# LyteLab_Base_Rev4.net
KiCad netlist of a schematic drawn in EAGLE
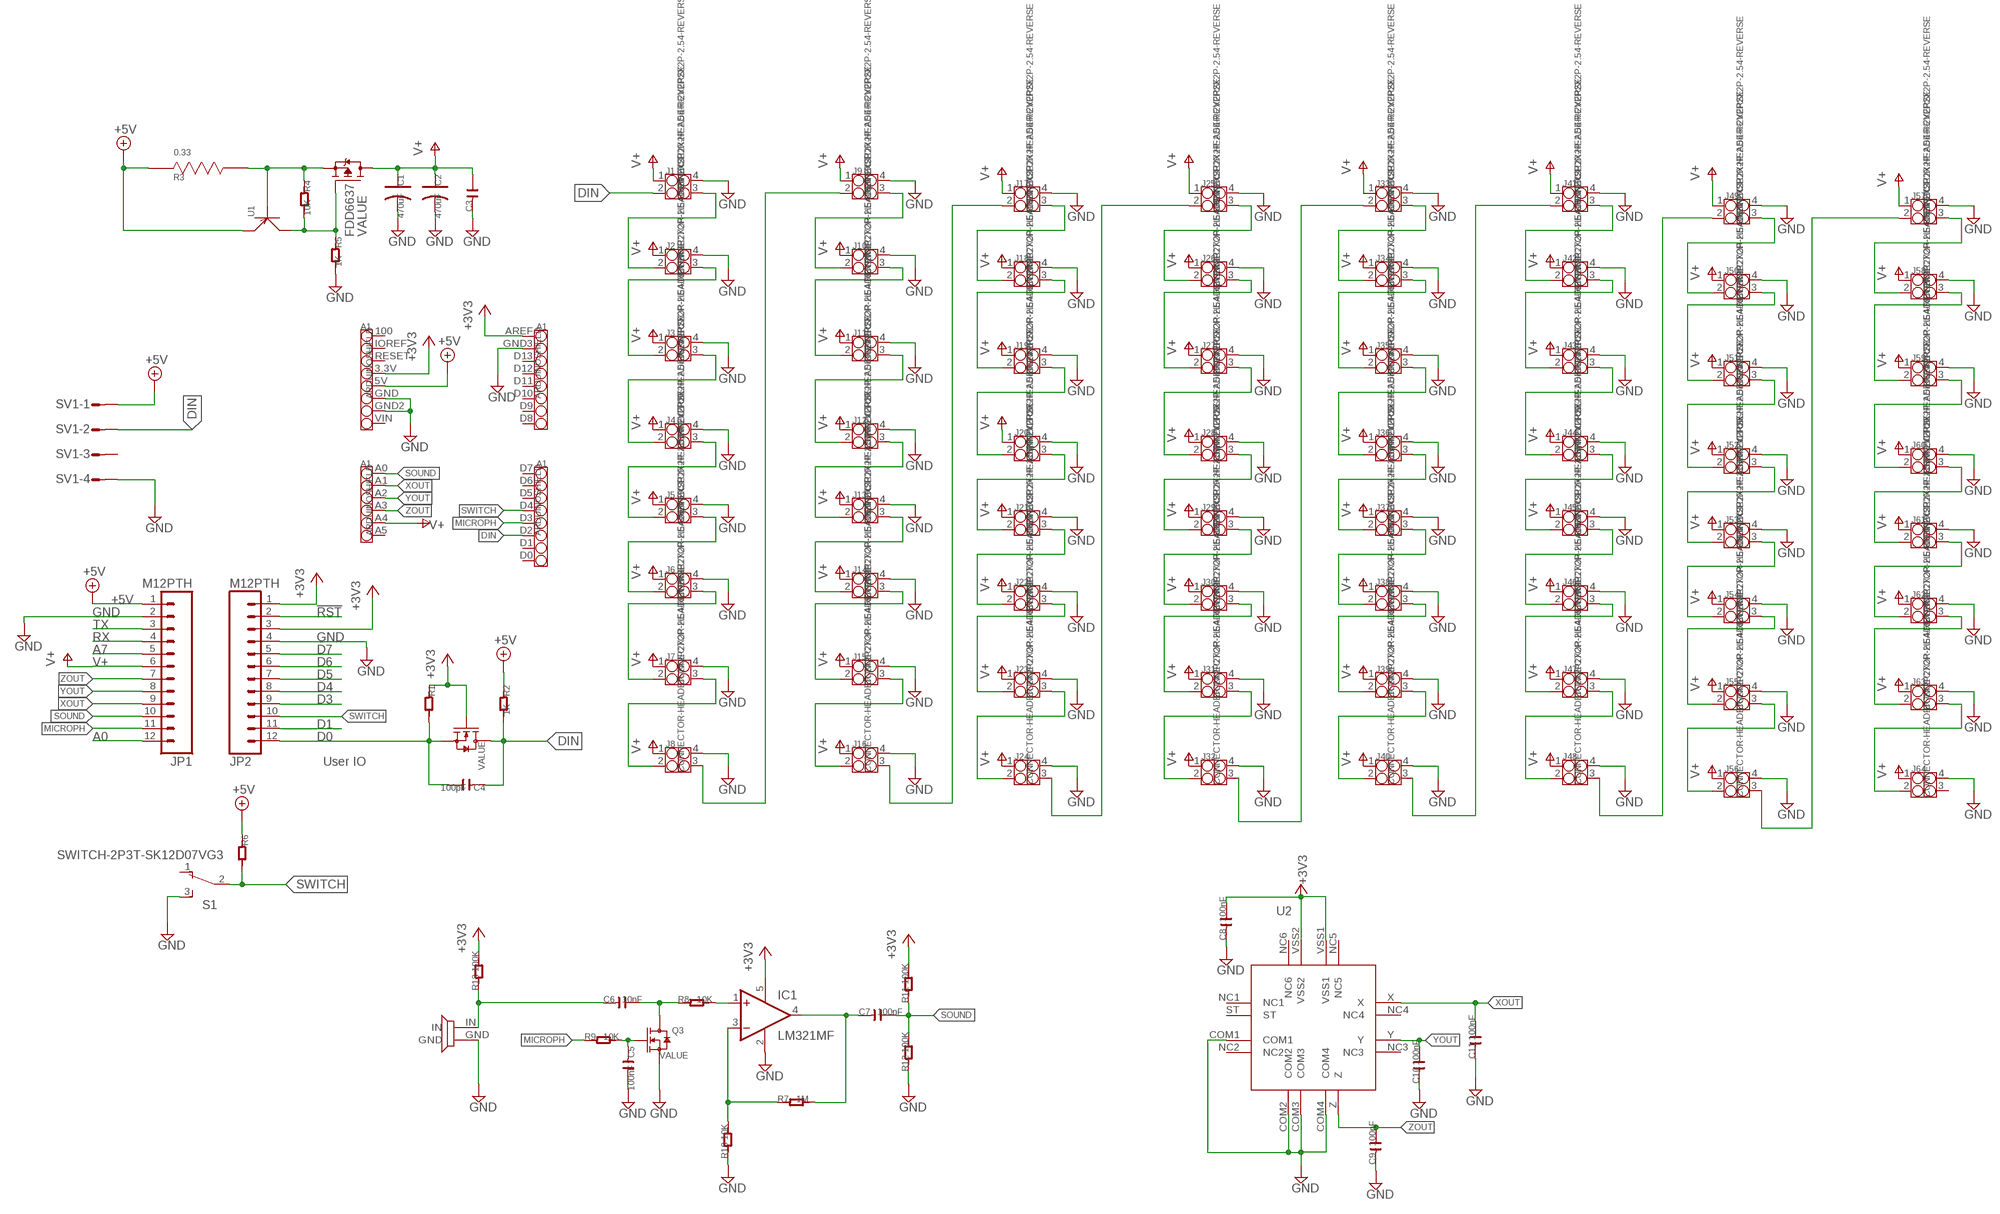
[diagram p0: schematic, sheet 1]

(export (version "E")
  (design (tool "Eeschema 10.0.6"))
  (components
    (comp (ref "2N7002")
      (value "MOSFET-N-044020001")
      (footprint "eagle-import:SOT23")
      (libsource (lib "eagle-import") (part "MOSFET-N-044020001"))
    )
    (comp (ref "A1")
      (value "ARDUINOSHIELD")
      (footprint "eagle-import:ARDUINOSHIELD")
      (libsource (lib "eagle-import") (part "ARDUINOSHIELD"))
    )
    (comp (ref "C1")
      (value "470uF")
      (footprint "eagle-import:CAPACITOR-E5-8.5")
      (libsource (lib "eagle-import") (part "C-POLARCAPACITOR-E5-8.5"))
    )
    (comp (ref "C2")
      (value "470uF")
      (footprint "eagle-import:CAPACITOR-E5-8.5")
      (libsource (lib "eagle-import") (part "C-POLARCAPACITOR-E5-8.5"))
    )
    (comp (ref "C3")
      (value "C-0603")
      (footprint "eagle-import:C0603")
      (libsource (lib "eagle-import") (part "C-0603"))
    )
    (comp (ref "C4")
      (value "100pF")
      (footprint "eagle-import:C0603")
      (libsource (lib "eagle-import") (part "C-0603"))
    )
    (comp (ref "C5")
      (value "100nF")
      (footprint "eagle-import:C0603")
      (libsource (lib "eagle-import") (part "C-0603"))
    )
    (comp (ref "C6")
      (value "10nF")
      (footprint "eagle-import:C0603")
      (libsource (lib "eagle-import") (part "C-0603"))
    )
    (comp (ref "C7")
      (value "100nF")
      (footprint "eagle-import:C0603")
      (libsource (lib "eagle-import") (part "C-0603"))
    )
    (comp (ref "C8")
      (value "100nF")
      (footprint "eagle-import:C0603")
      (libsource (lib "eagle-import") (part "C-0603"))
    )
    (comp (ref "C9")
      (value "100nF")
      (footprint "eagle-import:C0603")
      (libsource (lib "eagle-import") (part "C-0603"))
    )
    (comp (ref "C10")
      (value "100nF")
      (footprint "eagle-import:C0603")
      (libsource (lib "eagle-import") (part "C-0603"))
    )
    (comp (ref "C11")
      (value "100nF")
      (footprint "eagle-import:C0603")
      (libsource (lib "eagle-import") (part "C-0603"))
    )
    (comp (ref "FDD6637")
      (value "FDD4141TO252")
      (footprint "eagle-import:TO252")
      (libsource (lib "eagle-import") (part "FDD4141TO252"))
    )
    (comp (ref "IC1")
      (value "LM321MF")
      (footprint "eagle-import:SOT23-5")
      (libsource (lib "eagle-import") (part "LM321?MF"))
    )
    (comp (ref "J1")
      (value "CONNECTOR-HEADER-2X2P2X2P-2.54-REVERSE")
      (footprint "eagle-import:2X2P-2.54-REVERSE")
      (libsource (lib "eagle-import") (part "CONNECTOR-HEADER-2X2P2X2P-2.54-REVERSE"))
    )
    (comp (ref "J2")
      (value "CONNECTOR-HEADER-2X2P2X2P-2.54-REVERSE")
      (footprint "eagle-import:2X2P-2.54-REVERSE")
      (libsource (lib "eagle-import") (part "CONNECTOR-HEADER-2X2P2X2P-2.54-REVERSE"))
    )
    (comp (ref "J3")
      (value "CONNECTOR-HEADER-2X2P2X2P-2.54-REVERSE")
      (footprint "eagle-import:2X2P-2.54-REVERSE")
      (libsource (lib "eagle-import") (part "CONNECTOR-HEADER-2X2P2X2P-2.54-REVERSE"))
    )
    (comp (ref "J4")
      (value "CONNECTOR-HEADER-2X2P2X2P-2.54-REVERSE")
      (footprint "eagle-import:2X2P-2.54-REVERSE")
      (libsource (lib "eagle-import") (part "CONNECTOR-HEADER-2X2P2X2P-2.54-REVERSE"))
    )
    (comp (ref "J5")
      (value "CONNECTOR-HEADER-2X2P2X2P-2.54-REVERSE")
      (footprint "eagle-import:2X2P-2.54-REVERSE")
      (libsource (lib "eagle-import") (part "CONNECTOR-HEADER-2X2P2X2P-2.54-REVERSE"))
    )
    (comp (ref "J6")
      (value "CONNECTOR-HEADER-2X2P2X2P-2.54-REVERSE")
      (footprint "eagle-import:2X2P-2.54-REVERSE")
      (libsource (lib "eagle-import") (part "CONNECTOR-HEADER-2X2P2X2P-2.54-REVERSE"))
    )
    (comp (ref "J7")
      (value "CONNECTOR-HEADER-2X2P2X2P-2.54-REVERSE")
      (footprint "eagle-import:2X2P-2.54-REVERSE")
      (libsource (lib "eagle-import") (part "CONNECTOR-HEADER-2X2P2X2P-2.54-REVERSE"))
    )
    (comp (ref "J8")
      (value "CONNECTOR-HEADER-2X2P2X2P-2.54-REVERSE")
      (footprint "eagle-import:2X2P-2.54-REVERSE")
      (libsource (lib "eagle-import") (part "CONNECTOR-HEADER-2X2P2X2P-2.54-REVERSE"))
    )
    (comp (ref "J9")
      (value "CONNECTOR-HEADER-2X2P2X2P-2.54-REVERSE")
      (footprint "eagle-import:2X2P-2.54-REVERSE")
      (libsource (lib "eagle-import") (part "CONNECTOR-HEADER-2X2P2X2P-2.54-REVERSE"))
    )
    (comp (ref "J10")
      (value "CONNECTOR-HEADER-2X2P2X2P-2.54-REVERSE")
      (footprint "eagle-import:2X2P-2.54-REVERSE")
      (libsource (lib "eagle-import") (part "CONNECTOR-HEADER-2X2P2X2P-2.54-REVERSE"))
    )
    (comp (ref "J11")
      (value "CONNECTOR-HEADER-2X2P2X2P-2.54-REVERSE")
      (footprint "eagle-import:2X2P-2.54-REVERSE")
      (libsource (lib "eagle-import") (part "CONNECTOR-HEADER-2X2P2X2P-2.54-REVERSE"))
    )
    (comp (ref "J12")
      (value "CONNECTOR-HEADER-2X2P2X2P-2.54-REVERSE")
      (footprint "eagle-import:2X2P-2.54-REVERSE")
      (libsource (lib "eagle-import") (part "CONNECTOR-HEADER-2X2P2X2P-2.54-REVERSE"))
    )
    (comp (ref "J13")
      (value "CONNECTOR-HEADER-2X2P2X2P-2.54-REVERSE")
      (footprint "eagle-import:2X2P-2.54-REVERSE")
      (libsource (lib "eagle-import") (part "CONNECTOR-HEADER-2X2P2X2P-2.54-REVERSE"))
    )
    (comp (ref "J14")
      (value "CONNECTOR-HEADER-2X2P2X2P-2.54-REVERSE")
      (footprint "eagle-import:2X2P-2.54-REVERSE")
      (libsource (lib "eagle-import") (part "CONNECTOR-HEADER-2X2P2X2P-2.54-REVERSE"))
    )
    (comp (ref "J15")
      (value "CONNECTOR-HEADER-2X2P2X2P-2.54-REVERSE")
      (footprint "eagle-import:2X2P-2.54-REVERSE")
      (libsource (lib "eagle-import") (part "CONNECTOR-HEADER-2X2P2X2P-2.54-REVERSE"))
    )
    (comp (ref "J16")
      (value "CONNECTOR-HEADER-2X2P2X2P-2.54-REVERSE")
      (footprint "eagle-import:2X2P-2.54-REVERSE")
      (libsource (lib "eagle-import") (part "CONNECTOR-HEADER-2X2P2X2P-2.54-REVERSE"))
    )
    (comp (ref "J17")
      (value "CONNECTOR-HEADER-2X2P2X2P-2.54-REVERSE")
      (footprint "eagle-import:2X2P-2.54-REVERSE")
      (libsource (lib "eagle-import") (part "CONNECTOR-HEADER-2X2P2X2P-2.54-REVERSE"))
    )
    (comp (ref "J18")
      (value "CONNECTOR-HEADER-2X2P2X2P-2.54-REVERSE")
      (footprint "eagle-import:2X2P-2.54-REVERSE")
      (libsource (lib "eagle-import") (part "CONNECTOR-HEADER-2X2P2X2P-2.54-REVERSE"))
    )
    (comp (ref "J19")
      (value "CONNECTOR-HEADER-2X2P2X2P-2.54-REVERSE")
      (footprint "eagle-import:2X2P-2.54-REVERSE")
      (libsource (lib "eagle-import") (part "CONNECTOR-HEADER-2X2P2X2P-2.54-REVERSE"))
    )
    (comp (ref "J20")
      (value "CONNECTOR-HEADER-2X2P2X2P-2.54-REVERSE")
      (footprint "eagle-import:2X2P-2.54-REVERSE")
      (libsource (lib "eagle-import") (part "CONNECTOR-HEADER-2X2P2X2P-2.54-REVERSE"))
    )
    (comp (ref "J21")
      (value "CONNECTOR-HEADER-2X2P2X2P-2.54-REVERSE")
      (footprint "eagle-import:2X2P-2.54-REVERSE")
      (libsource (lib "eagle-import") (part "CONNECTOR-HEADER-2X2P2X2P-2.54-REVERSE"))
    )
    (comp (ref "J22")
      (value "CONNECTOR-HEADER-2X2P2X2P-2.54-REVERSE")
      (footprint "eagle-import:2X2P-2.54-REVERSE")
      (libsource (lib "eagle-import") (part "CONNECTOR-HEADER-2X2P2X2P-2.54-REVERSE"))
    )
    (comp (ref "J23")
      (value "CONNECTOR-HEADER-2X2P2X2P-2.54-REVERSE")
      (footprint "eagle-import:2X2P-2.54-REVERSE")
      (libsource (lib "eagle-import") (part "CONNECTOR-HEADER-2X2P2X2P-2.54-REVERSE"))
    )
    (comp (ref "J24")
      (value "CONNECTOR-HEADER-2X2P2X2P-2.54-REVERSE")
      (footprint "eagle-import:2X2P-2.54-REVERSE")
      (libsource (lib "eagle-import") (part "CONNECTOR-HEADER-2X2P2X2P-2.54-REVERSE"))
    )
    (comp (ref "J25")
      (value "CONNECTOR-HEADER-2X2P2X2P-2.54-REVERSE")
      (footprint "eagle-import:2X2P-2.54-REVERSE")
      (libsource (lib "eagle-import") (part "CONNECTOR-HEADER-2X2P2X2P-2.54-REVERSE"))
    )
    (comp (ref "J26")
      (value "CONNECTOR-HEADER-2X2P2X2P-2.54-REVERSE")
      (footprint "eagle-import:2X2P-2.54-REVERSE")
      (libsource (lib "eagle-import") (part "CONNECTOR-HEADER-2X2P2X2P-2.54-REVERSE"))
    )
    (comp (ref "J27")
      (value "CONNECTOR-HEADER-2X2P2X2P-2.54-REVERSE")
      (footprint "eagle-import:2X2P-2.54-REVERSE")
      (libsource (lib "eagle-import") (part "CONNECTOR-HEADER-2X2P2X2P-2.54-REVERSE"))
    )
    (comp (ref "J28")
      (value "CONNECTOR-HEADER-2X2P2X2P-2.54-REVERSE")
      (footprint "eagle-import:2X2P-2.54-REVERSE")
      (libsource (lib "eagle-import") (part "CONNECTOR-HEADER-2X2P2X2P-2.54-REVERSE"))
    )
    (comp (ref "J29")
      (value "CONNECTOR-HEADER-2X2P2X2P-2.54-REVERSE")
      (footprint "eagle-import:2X2P-2.54-REVERSE")
      (libsource (lib "eagle-import") (part "CONNECTOR-HEADER-2X2P2X2P-2.54-REVERSE"))
    )
    (comp (ref "J30")
      (value "CONNECTOR-HEADER-2X2P2X2P-2.54-REVERSE")
      (footprint "eagle-import:2X2P-2.54-REVERSE")
      (libsource (lib "eagle-import") (part "CONNECTOR-HEADER-2X2P2X2P-2.54-REVERSE"))
    )
    (comp (ref "J31")
      (value "CONNECTOR-HEADER-2X2P2X2P-2.54-REVERSE")
      (footprint "eagle-import:2X2P-2.54-REVERSE")
      (libsource (lib "eagle-import") (part "CONNECTOR-HEADER-2X2P2X2P-2.54-REVERSE"))
    )
    (comp (ref "J32")
      (value "CONNECTOR-HEADER-2X2P2X2P-2.54-REVERSE")
      (footprint "eagle-import:2X2P-2.54-REVERSE")
      (libsource (lib "eagle-import") (part "CONNECTOR-HEADER-2X2P2X2P-2.54-REVERSE"))
    )
    (comp (ref "J33")
      (value "CONNECTOR-HEADER-2X2P2X2P-2.54-REVERSE")
      (footprint "eagle-import:2X2P-2.54-REVERSE")
      (libsource (lib "eagle-import") (part "CONNECTOR-HEADER-2X2P2X2P-2.54-REVERSE"))
    )
    (comp (ref "J34")
      (value "CONNECTOR-HEADER-2X2P2X2P-2.54-REVERSE")
      (footprint "eagle-import:2X2P-2.54-REVERSE")
      (libsource (lib "eagle-import") (part "CONNECTOR-HEADER-2X2P2X2P-2.54-REVERSE"))
    )
    (comp (ref "J35")
      (value "CONNECTOR-HEADER-2X2P2X2P-2.54-REVERSE")
      (footprint "eagle-import:2X2P-2.54-REVERSE")
      (libsource (lib "eagle-import") (part "CONNECTOR-HEADER-2X2P2X2P-2.54-REVERSE"))
    )
    (comp (ref "J36")
      (value "CONNECTOR-HEADER-2X2P2X2P-2.54-REVERSE")
      (footprint "eagle-import:2X2P-2.54-REVERSE")
      (libsource (lib "eagle-import") (part "CONNECTOR-HEADER-2X2P2X2P-2.54-REVERSE"))
    )
    (comp (ref "J37")
      (value "CONNECTOR-HEADER-2X2P2X2P-2.54-REVERSE")
      (footprint "eagle-import:2X2P-2.54-REVERSE")
      (libsource (lib "eagle-import") (part "CONNECTOR-HEADER-2X2P2X2P-2.54-REVERSE"))
    )
    (comp (ref "J38")
      (value "CONNECTOR-HEADER-2X2P2X2P-2.54-REVERSE")
      (footprint "eagle-import:2X2P-2.54-REVERSE")
      (libsource (lib "eagle-import") (part "CONNECTOR-HEADER-2X2P2X2P-2.54-REVERSE"))
    )
    (comp (ref "J39")
      (value "CONNECTOR-HEADER-2X2P2X2P-2.54-REVERSE")
      (footprint "eagle-import:2X2P-2.54-REVERSE")
      (libsource (lib "eagle-import") (part "CONNECTOR-HEADER-2X2P2X2P-2.54-REVERSE"))
    )
    (comp (ref "J40")
      (value "CONNECTOR-HEADER-2X2P2X2P-2.54-REVERSE")
      (footprint "eagle-import:2X2P-2.54-REVERSE")
      (libsource (lib "eagle-import") (part "CONNECTOR-HEADER-2X2P2X2P-2.54-REVERSE"))
    )
    (comp (ref "J41")
      (value "CONNECTOR-HEADER-2X2P2X2P-2.54-REVERSE")
      (footprint "eagle-import:2X2P-2.54-REVERSE")
      (libsource (lib "eagle-import") (part "CONNECTOR-HEADER-2X2P2X2P-2.54-REVERSE"))
    )
    (comp (ref "J42")
      (value "CONNECTOR-HEADER-2X2P2X2P-2.54-REVERSE")
      (footprint "eagle-import:2X2P-2.54-REVERSE")
      (libsource (lib "eagle-import") (part "CONNECTOR-HEADER-2X2P2X2P-2.54-REVERSE"))
    )
    (comp (ref "J43")
      (value "CONNECTOR-HEADER-2X2P2X2P-2.54-REVERSE")
      (footprint "eagle-import:2X2P-2.54-REVERSE")
      (libsource (lib "eagle-import") (part "CONNECTOR-HEADER-2X2P2X2P-2.54-REVERSE"))
    )
    (comp (ref "J44")
      (value "CONNECTOR-HEADER-2X2P2X2P-2.54-REVERSE")
      (footprint "eagle-import:2X2P-2.54-REVERSE")
      (libsource (lib "eagle-import") (part "CONNECTOR-HEADER-2X2P2X2P-2.54-REVERSE"))
    )
    (comp (ref "J45")
      (value "CONNECTOR-HEADER-2X2P2X2P-2.54-REVERSE")
      (footprint "eagle-import:2X2P-2.54-REVERSE")
      (libsource (lib "eagle-import") (part "CONNECTOR-HEADER-2X2P2X2P-2.54-REVERSE"))
    )
    (comp (ref "J46")
      (value "CONNECTOR-HEADER-2X2P2X2P-2.54-REVERSE")
      (footprint "eagle-import:2X2P-2.54-REVERSE")
      (libsource (lib "eagle-import") (part "CONNECTOR-HEADER-2X2P2X2P-2.54-REVERSE"))
    )
    (comp (ref "J47")
      (value "CONNECTOR-HEADER-2X2P2X2P-2.54-REVERSE")
      (footprint "eagle-import:2X2P-2.54-REVERSE")
      (libsource (lib "eagle-import") (part "CONNECTOR-HEADER-2X2P2X2P-2.54-REVERSE"))
    )
    (comp (ref "J48")
      (value "CONNECTOR-HEADER-2X2P2X2P-2.54-REVERSE")
      (footprint "eagle-import:2X2P-2.54-REVERSE")
      (libsource (lib "eagle-import") (part "CONNECTOR-HEADER-2X2P2X2P-2.54-REVERSE"))
    )
    (comp (ref "J49")
      (value "CONNECTOR-HEADER-2X2P2X2P-2.54-REVERSE")
      (footprint "eagle-import:2X2P-2.54-REVERSE")
      (libsource (lib "eagle-import") (part "CONNECTOR-HEADER-2X2P2X2P-2.54-REVERSE"))
    )
    (comp (ref "J50")
      (value "CONNECTOR-HEADER-2X2P2X2P-2.54-REVERSE")
      (footprint "eagle-import:2X2P-2.54-REVERSE")
      (libsource (lib "eagle-import") (part "CONNECTOR-HEADER-2X2P2X2P-2.54-REVERSE"))
    )
    (comp (ref "J51")
      (value "CONNECTOR-HEADER-2X2P2X2P-2.54-REVERSE")
      (footprint "eagle-import:2X2P-2.54-REVERSE")
      (libsource (lib "eagle-import") (part "CONNECTOR-HEADER-2X2P2X2P-2.54-REVERSE"))
    )
    (comp (ref "J52")
      (value "CONNECTOR-HEADER-2X2P2X2P-2.54-REVERSE")
      (footprint "eagle-import:2X2P-2.54-REVERSE")
      (libsource (lib "eagle-import") (part "CONNECTOR-HEADER-2X2P2X2P-2.54-REVERSE"))
    )
    (comp (ref "J53")
      (value "CONNECTOR-HEADER-2X2P2X2P-2.54-REVERSE")
      (footprint "eagle-import:2X2P-2.54-REVERSE")
      (libsource (lib "eagle-import") (part "CONNECTOR-HEADER-2X2P2X2P-2.54-REVERSE"))
    )
    (comp (ref "J54")
      (value "CONNECTOR-HEADER-2X2P2X2P-2.54-REVERSE")
      (footprint "eagle-import:2X2P-2.54-REVERSE")
      (libsource (lib "eagle-import") (part "CONNECTOR-HEADER-2X2P2X2P-2.54-REVERSE"))
    )
    (comp (ref "J55")
      (value "CONNECTOR-HEADER-2X2P2X2P-2.54-REVERSE")
      (footprint "eagle-import:2X2P-2.54-REVERSE")
      (libsource (lib "eagle-import") (part "CONNECTOR-HEADER-2X2P2X2P-2.54-REVERSE"))
    )
    (comp (ref "J56")
      (value "CONNECTOR-HEADER-2X2P2X2P-2.54-REVERSE")
      (footprint "eagle-import:2X2P-2.54-REVERSE")
      (libsource (lib "eagle-import") (part "CONNECTOR-HEADER-2X2P2X2P-2.54-REVERSE"))
    )
    (comp (ref "J57")
      (value "CONNECTOR-HEADER-2X2P2X2P-2.54-REVERSE")
      (footprint "eagle-import:2X2P-2.54-REVERSE")
      (libsource (lib "eagle-import") (part "CONNECTOR-HEADER-2X2P2X2P-2.54-REVERSE"))
    )
    (comp (ref "J58")
      (value "CONNECTOR-HEADER-2X2P2X2P-2.54-REVERSE")
      (footprint "eagle-import:2X2P-2.54-REVERSE")
      (libsource (lib "eagle-import") (part "CONNECTOR-HEADER-2X2P2X2P-2.54-REVERSE"))
    )
    (comp (ref "J59")
      (value "CONNECTOR-HEADER-2X2P2X2P-2.54-REVERSE")
      (footprint "eagle-import:2X2P-2.54-REVERSE")
      (libsource (lib "eagle-import") (part "CONNECTOR-HEADER-2X2P2X2P-2.54-REVERSE"))
    )
    (comp (ref "J60")
      (value "CONNECTOR-HEADER-2X2P2X2P-2.54-REVERSE")
      (footprint "eagle-import:2X2P-2.54-REVERSE")
      (libsource (lib "eagle-import") (part "CONNECTOR-HEADER-2X2P2X2P-2.54-REVERSE"))
    )
    (comp (ref "J61")
      (value "CONNECTOR-HEADER-2X2P2X2P-2.54-REVERSE")
      (footprint "eagle-import:2X2P-2.54-REVERSE")
      (libsource (lib "eagle-import") (part "CONNECTOR-HEADER-2X2P2X2P-2.54-REVERSE"))
    )
    (comp (ref "J62")
      (value "CONNECTOR-HEADER-2X2P2X2P-2.54-REVERSE")
      (footprint "eagle-import:2X2P-2.54-REVERSE")
      (libsource (lib "eagle-import") (part "CONNECTOR-HEADER-2X2P2X2P-2.54-REVERSE"))
    )
    (comp (ref "J63")
      (value "CONNECTOR-HEADER-2X2P2X2P-2.54-REVERSE")
      (footprint "eagle-import:2X2P-2.54-REVERSE")
      (libsource (lib "eagle-import") (part "CONNECTOR-HEADER-2X2P2X2P-2.54-REVERSE"))
    )
    (comp (ref "J64")
      (value "CONNECTOR-HEADER-2X2P2X2P-2.54-REVERSE")
      (footprint "eagle-import:2X2P-2.54-REVERSE")
      (libsource (lib "eagle-import") (part "CONNECTOR-HEADER-2X2P2X2P-2.54-REVERSE"))
    )
    (comp (ref "JP1")
      (value "M12PTH")
      (footprint "eagle-import:1X12-SMALL-PADS")
      (libsource (lib "eagle-import") (part "M12PTH"))
    )
    (comp (ref "JP2")
      (value "M12PTH")
      (footprint "eagle-import:1X12-SMALL-PADS")
      (libsource (lib "eagle-import") (part "M12PTH"))
    )
    (comp (ref "Q3")
      (value "MOSFET-N-044020001")
      (footprint "eagle-import:SOT23")
      (libsource (lib "eagle-import") (part "MOSFET-N-044020001"))
    )
    (comp (ref "R1")
      (value "R-0603")
      (footprint "eagle-import:R0603")
      (libsource (lib "eagle-import") (part "R-0603"))
    )
    (comp (ref "R2")
      (value "1K")
      (footprint "eagle-import:R0603")
      (libsource (lib "eagle-import") (part "R-0603"))
    )
    (comp (ref "R3")
      (value "0.33")
      (footprint "eagle-import:RESISTOR-3W-20MM")
      (libsource (lib "eagle-import") (part "RESISTOR-3W-20MM"))
    )
    (comp (ref "R4")
      (value "10K")
      (footprint "eagle-import:R0603")
      (libsource (lib "eagle-import") (part "R-0603"))
    )
    (comp (ref "R5")
      (value "1K")
      (footprint "eagle-import:R0603")
      (libsource (lib "eagle-import") (part "R-0603"))
    )
    (comp (ref "R6")
      (value "R-0603")
      (footprint "eagle-import:R0603")
      (libsource (lib "eagle-import") (part "R-0603"))
    )
    (comp (ref "R7")
      (value "1M")
      (footprint "eagle-import:R0603")
      (libsource (lib "eagle-import") (part "R-0603"))
    )
    (comp (ref "R8")
      (value "10K")
      (footprint "eagle-import:R0603")
      (libsource (lib "eagle-import") (part "R-0603"))
    )
    (comp (ref "R9")
      (value "10K")
      (footprint "eagle-import:R0603")
      (libsource (lib "eagle-import") (part "R-0603"))
    )
    (comp (ref "R10")
      (value "10K")
      (footprint "eagle-import:R0603")
      (libsource (lib "eagle-import") (part "R-0603"))
    )
    (comp (ref "R11")
      (value "100K")
      (footprint "eagle-import:R0603")
      (libsource (lib "eagle-import") (part "R-0603"))
    )
    (comp (ref "R12")
      (value "100K")
      (footprint "eagle-import:R0603")
      (libsource (lib "eagle-import") (part "R-0603"))
    )
    (comp (ref "R13")
      (value "100K")
      (footprint "eagle-import:R0603")
      (libsource (lib "eagle-import") (part "R-0603"))
    )
    (comp (ref "S1")
      (value "SWITCH-2P3T-SK12D07VG3")
      (footprint "eagle-import:SWITCH-2P3T-SK12D07VG3")
      (libsource (lib "eagle-import") (part "SWITCH-2P3T-SK12D07VG3"))
    )
    (comp (ref "SV1")
      (value "S04P")
      (footprint "eagle-import:S04P")
      (libsource (lib "eagle-import") (part "S04P"))
    )
    (comp (ref "U$1")
      (value "MICROPHONE")
      (footprint "eagle-import:MICROPHONE")
      (libsource (lib "eagle-import") (part "MICROPHONE"))
    )
    (comp (ref "U1")
      (value "TRANSISTOR-PNP-041003001")
      (footprint "eagle-import:SOT23")
      (libsource (lib "eagle-import") (part "TRANSISTOR-PNP-041003001"))
    )
    (comp (ref "U2")
      (value "ADXL335")
      (footprint "eagle-import:ADXL335")
      (libsource (lib "eagle-import") (part "ADXL335"))
    )
  )
  (nets
    (net (code "1") (name "+3V3") (class "Default")
      (node (ref "2N7002") (pin "1") (pinfunction "G_1") (pintype "passive"))
      (node (ref "A1") (pin "3.3V") (pinfunction "3.3V_3.3V") (pintype "bidirectional"))
      (node (ref "A1") (pin "AREF") (pinfunction "AREF_AREF") (pintype "bidirectional"))
      (node (ref "C8") (pin "2") (pinfunction "2_2") (pintype "bidirectional"))
      (node (ref "IC1") (pin "5") (pinfunction "V+_5") (pintype "power_in"))
      (node (ref "JP2") (pin "1") (pinfunction "1_1") (pintype "passive"))
      (node (ref "JP2") (pin "3") (pinfunction "3_3") (pintype "passive"))
      (node (ref "R1") (pin "1") (pinfunction "1_1") (pintype "bidirectional"))
      (node (ref "R11") (pin "2") (pinfunction "2_2") (pintype "bidirectional"))
      (node (ref "R13") (pin "2") (pinfunction "2_2") (pintype "bidirectional"))
      (node (ref "U2") (pin "VSS1") (pinfunction "VSS1_VSS1") (pintype "bidirectional"))
      (node (ref "U2") (pin "VSS2") (pinfunction "VSS2_VSS2") (pintype "bidirectional"))
    )
    (net (code "2") (name "+5V") (class "Default")
      (node (ref "A1") (pin "5V") (pinfunction "5V_5V") (pintype "bidirectional"))
      (node (ref "JP1") (pin "1") (pinfunction "1_1") (pintype "passive"))
      (node (ref "R2") (pin "1") (pinfunction "1_1") (pintype "bidirectional"))
      (node (ref "R3") (pin "1") (pinfunction "1_1") (pintype "bidirectional"))
      (node (ref "R6") (pin "1") (pinfunction "1_1") (pintype "bidirectional"))
      (node (ref "SV1") (pin "1") (pinfunction "S_1") (pintype "passive"))
      (node (ref "U1") (pin "2") (pinfunction "E_2") (pintype "passive"))
    )
    (net (code "3") (name "/A0") (class "Default")
      (node (ref "JP1") (pin "12") (pinfunction "12_12") (pintype "passive"))
    )
    (net (code "4") (name "/A7") (class "Default")
      (node (ref "JP1") (pin "5") (pinfunction "5_5") (pintype "passive"))
    )
    (net (code "5") (name "/D0") (class "Default")
      (node (ref "2N7002") (pin "2") (pinfunction "S_2") (pintype "passive"))
      (node (ref "C4") (pin "2") (pinfunction "2_2") (pintype "bidirectional"))
      (node (ref "JP2") (pin "12") (pinfunction "12_12") (pintype "passive"))
      (node (ref "R1") (pin "2") (pinfunction "2_2") (pintype "bidirectional"))
    )
    (net (code "6") (name "/D1") (class "Default")
      (node (ref "JP2") (pin "11") (pinfunction "11_11") (pintype "passive"))
    )
    (net (code "7") (name "/D3") (class "Default")
      (node (ref "JP2") (pin "9") (pinfunction "9_9") (pintype "passive"))
    )
    (net (code "8") (name "/D4") (class "Default")
      (node (ref "JP2") (pin "8") (pinfunction "8_8") (pintype "passive"))
    )
    (net (code "9") (name "/D5") (class "Default")
      (node (ref "JP2") (pin "7") (pinfunction "7_7") (pintype "passive"))
    )
    (net (code "10") (name "/D6") (class "Default")
      (node (ref "JP2") (pin "6") (pinfunction "6_6") (pintype "passive"))
    )
    (net (code "11") (name "/D7") (class "Default")
      (node (ref "JP2") (pin "5") (pinfunction "5_5") (pintype "passive"))
    )
    (net (code "12") (name "/RX") (class "Default")
      (node (ref "JP1") (pin "4") (pinfunction "4_4") (pintype "passive"))
    )
    (net (code "13") (name "/TX") (class "Default")
      (node (ref "JP1") (pin "3") (pinfunction "3_3") (pintype "passive"))
    )
    (net (code "14") (name "/~{RST}") (class "Default")
      (node (ref "JP2") (pin "2") (pinfunction "2_2") (pintype "passive"))
    )
    (net (code "15") (name "DIN") (class "Default")
      (node (ref "2N7002") (pin "3") (pinfunction "D_3") (pintype "passive"))
      (node (ref "A1") (pin "D2") (pinfunction "D2_D2") (pintype "bidirectional"))
      (node (ref "C4") (pin "1") (pinfunction "1_1") (pintype "bidirectional"))
      (node (ref "J1") (pin "2") (pinfunction "2_2") (pintype "bidirectional"))
      (node (ref "R2") (pin "2") (pinfunction "2_2") (pintype "bidirectional"))
      (node (ref "SV1") (pin "2") (pinfunction "S_2") (pintype "passive"))
    )
    (net (code "16") (name "GND") (class "Default")
      (node (ref "A1") (pin "GND") (pinfunction "GND_GND") (pintype "bidirectional"))
      (node (ref "A1") (pin "GND2") (pinfunction "GND2_GND2") (pintype "bidirectional"))
      (node (ref "A1") (pin "GND3") (pinfunction "GND3_GND3") (pintype "bidirectional"))
      (node (ref "C1") (pin "-") (pinfunction "2_-") (pintype "bidirectional"))
      (node (ref "C10") (pin "1") (pinfunction "1_1") (pintype "bidirectional"))
      (node (ref "C11") (pin "1") (pinfunction "1_1") (pintype "bidirectional"))
      (node (ref "C2") (pin "-") (pinfunction "2_-") (pintype "bidirectional"))
      (node (ref "C3") (pin "1") (pinfunction "1_1") (pintype "bidirectional"))
      (node (ref "C5") (pin "2") (pinfunction "2_2") (pintype "bidirectional"))
      (node (ref "C8") (pin "1") (pinfunction "1_1") (pintype "bidirectional"))
      (node (ref "C9") (pin "1") (pinfunction "1_1") (pintype "bidirectional"))
      (node (ref "IC1") (pin "2") (pinfunction "V-_2") (pintype "power_in"))
      (node (ref "J1") (pin "4") (pinfunction "4_4") (pintype "bidirectional"))
      (node (ref "J10") (pin "4") (pinfunction "4_4") (pintype "bidirectional"))
      (node (ref "J11") (pin "4") (pinfunction "4_4") (pintype "bidirectional"))
      (node (ref "J12") (pin "4") (pinfunction "4_4") (pintype "bidirectional"))
      (node (ref "J13") (pin "4") (pinfunction "4_4") (pintype "bidirectional"))
      (node (ref "J14") (pin "4") (pinfunction "4_4") (pintype "bidirectional"))
      (node (ref "J15") (pin "4") (pinfunction "4_4") (pintype "bidirectional"))
      (node (ref "J16") (pin "4") (pinfunction "4_4") (pintype "bidirectional"))
      (node (ref "J17") (pin "4") (pinfunction "4_4") (pintype "bidirectional"))
      (node (ref "J18") (pin "4") (pinfunction "4_4") (pintype "bidirectional"))
      (node (ref "J19") (pin "4") (pinfunction "4_4") (pintype "bidirectional"))
      (node (ref "J2") (pin "4") (pinfunction "4_4") (pintype "bidirectional"))
      (node (ref "J20") (pin "4") (pinfunction "4_4") (pintype "bidirectional"))
      (node (ref "J21") (pin "4") (pinfunction "4_4") (pintype "bidirectional"))
      (node (ref "J22") (pin "4") (pinfunction "4_4") (pintype "bidirectional"))
      (node (ref "J23") (pin "4") (pinfunction "4_4") (pintype "bidirectional"))
      (node (ref "J24") (pin "4") (pinfunction "4_4") (pintype "bidirectional"))
      (node (ref "J25") (pin "4") (pinfunction "4_4") (pintype "bidirectional"))
      (node (ref "J26") (pin "4") (pinfunction "4_4") (pintype "bidirectional"))
      (node (ref "J27") (pin "4") (pinfunction "4_4") (pintype "bidirectional"))
      (node (ref "J28") (pin "4") (pinfunction "4_4") (pintype "bidirectional"))
      (node (ref "J29") (pin "4") (pinfunction "4_4") (pintype "bidirectional"))
      (node (ref "J3") (pin "4") (pinfunction "4_4") (pintype "bidirectional"))
      (node (ref "J30") (pin "4") (pinfunction "4_4") (pintype "bidirectional"))
      (node (ref "J31") (pin "4") (pinfunction "4_4") (pintype "bidirectional"))
      (node (ref "J32") (pin "4") (pinfunction "4_4") (pintype "bidirectional"))
      (node (ref "J33") (pin "4") (pinfunction "4_4") (pintype "bidirectional"))
      (node (ref "J34") (pin "4") (pinfunction "4_4") (pintype "bidirectional"))
      (node (ref "J35") (pin "4") (pinfunction "4_4") (pintype "bidirectional"))
      (node (ref "J36") (pin "4") (pinfunction "4_4") (pintype "bidirectional"))
      (node (ref "J37") (pin "4") (pinfunction "4_4") (pintype "bidirectional"))
      (node (ref "J38") (pin "4") (pinfunction "4_4") (pintype "bidirectional"))
      (node (ref "J39") (pin "4") (pinfunction "4_4") (pintype "bidirectional"))
      (node (ref "J4") (pin "4") (pinfunction "4_4") (pintype "bidirectional"))
      (node (ref "J40") (pin "4") (pinfunction "4_4") (pintype "bidirectional"))
      (node (ref "J41") (pin "4") (pinfunction "4_4") (pintype "bidirectional"))
      (node (ref "J42") (pin "4") (pinfunction "4_4") (pintype "bidirectional"))
      (node (ref "J43") (pin "4") (pinfunction "4_4") (pintype "bidirectional"))
      (node (ref "J44") (pin "4") (pinfunction "4_4") (pintype "bidirectional"))
      (node (ref "J45") (pin "4") (pinfunction "4_4") (pintype "bidirectional"))
      (node (ref "J46") (pin "4") (pinfunction "4_4") (pintype "bidirectional"))
      (node (ref "J47") (pin "4") (pinfunction "4_4") (pintype "bidirectional"))
      (node (ref "J48") (pin "4") (pinfunction "4_4") (pintype "bidirectional"))
      (node (ref "J49") (pin "4") (pinfunction "4_4") (pintype "bidirectional"))
      (node (ref "J5") (pin "4") (pinfunction "4_4") (pintype "bidirectional"))
      (node (ref "J50") (pin "4") (pinfunction "4_4") (pintype "bidirectional"))
      (node (ref "J51") (pin "4") (pinfunction "4_4") (pintype "bidirectional"))
      (node (ref "J52") (pin "4") (pinfunction "4_4") (pintype "bidirectional"))
      (node (ref "J53") (pin "4") (pinfunction "4_4") (pintype "bidirectional"))
      (node (ref "J54") (pin "4") (pinfunction "4_4") (pintype "bidirectional"))
      (node (ref "J55") (pin "4") (pinfunction "4_4") (pintype "bidirectional"))
      (node (ref "J56") (pin "4") (pinfunction "4_4") (pintype "bidirectional"))
      (node (ref "J57") (pin "4") (pinfunction "4_4") (pintype "bidirectional"))
      (node (ref "J58") (pin "4") (pinfunction "4_4") (pintype "bidirectional"))
      (node (ref "J59") (pin "4") (pinfunction "4_4") (pintype "bidirectional"))
      (node (ref "J6") (pin "4") (pinfunction "4_4") (pintype "bidirectional"))
      (node (ref "J60") (pin "4") (pinfunction "4_4") (pintype "bidirectional"))
      (node (ref "J61") (pin "4") (pinfunction "4_4") (pintype "bidirectional"))
      (node (ref "J62") (pin "4") (pinfunction "4_4") (pintype "bidirectional"))
      (node (ref "J63") (pin "4") (pinfunction "4_4") (pintype "bidirectional"))
      (node (ref "J64") (pin "4") (pinfunction "4_4") (pintype "bidirectional"))
      (node (ref "J7") (pin "4") (pinfunction "4_4") (pintype "bidirectional"))
      (node (ref "J8") (pin "4") (pinfunction "4_4") (pintype "bidirectional"))
      (node (ref "J9") (pin "4") (pinfunction "4_4") (pintype "bidirectional"))
      (node (ref "JP1") (pin "2") (pinfunction "2_2") (pintype "passive"))
      (node (ref "JP2") (pin "4") (pinfunction "4_4") (pintype "passive"))
      (node (ref "Q3") (pin "2") (pinfunction "S_2") (pintype "passive"))
      (node (ref "R10") (pin "1") (pinfunction "1_1") (pintype "bidirectional"))
      (node (ref "R12") (pin "1") (pinfunction "1_1") (pintype "bidirectional"))
      (node (ref "R5") (pin "2") (pinfunction "2_2") (pintype "bidirectional"))
      (node (ref "S1") (pin "3") (pinfunction "S_3") (pintype "passive"))
      (node (ref "SV1") (pin "4") (pinfunction "S_4") (pintype "passive"))
      (node (ref "U$1") (pin "GND") (pinfunction "GND_GND") (pintype "bidirectional"))
      (node (ref "U2") (pin "COM1") (pinfunction "COM1_COM1") (pintype "bidirectional"))
      (node (ref "U2") (pin "COM2") (pinfunction "COM2_COM2") (pintype "bidirectional"))
      (node (ref "U2") (pin "COM3") (pinfunction "COM3_COM3") (pintype "bidirectional"))
      (node (ref "U2") (pin "COM4") (pinfunction "COM4_COM4") (pintype "bidirectional"))
    )
    (net (code "17") (name "MICROPH") (class "Default")
      (node (ref "A1") (pin "D3") (pinfunction "D3_D3") (pintype "bidirectional"))
      (node (ref "JP1") (pin "11") (pinfunction "11_11") (pintype "passive"))
      (node (ref "R9") (pin "1") (pinfunction "1_1") (pintype "bidirectional"))
    )
    (net (code "18") (name "Net-(C6-Pad1)") (class "Default")
      (node (ref "C6") (pin "1") (pinfunction "1_1") (pintype "bidirectional"))
      (node (ref "R13") (pin "1") (pinfunction "1_1") (pintype "bidirectional"))
      (node (ref "U$1") (pin "IN") (pinfunction "IN_IN") (pintype "bidirectional"))
    )
    (net (code "19") (name "Net-(FDD6637-G)") (class "Default")
      (node (ref "FDD6637") (pin "1") (pinfunction "G_1") (pintype "passive"))
      (node (ref "R4") (pin "2") (pinfunction "2_2") (pintype "bidirectional"))
      (node (ref "R5") (pin "1") (pinfunction "1_1") (pintype "bidirectional"))
      (node (ref "U1") (pin "3") (pinfunction "C_3") (pintype "passive"))
    )
    (net (code "20") (name "Net-(FDD6637-S)") (class "Default")
      (node (ref "FDD6637") (pin "2") (pinfunction "S_2") (pintype "passive"))
      (node (ref "R3") (pin "2") (pinfunction "2_2") (pintype "bidirectional"))
      (node (ref "R4") (pin "1") (pinfunction "1_1") (pintype "bidirectional"))
      (node (ref "U1") (pin "1") (pinfunction "B_1") (pintype "passive"))
    )
    (net (code "21") (name "Net-(IC1-+IN)") (class "Default")
      (node (ref "IC1") (pin "1") (pinfunction "+IN_1") (pintype "input"))
      (node (ref "R8") (pin "2") (pinfunction "2_2") (pintype "bidirectional"))
    )
    (net (code "22") (name "Net-(IC1--IN)") (class "Default")
      (node (ref "IC1") (pin "3") (pinfunction "-IN_3") (pintype "input"))
      (node (ref "R10") (pin "2") (pinfunction "2_2") (pintype "bidirectional"))
      (node (ref "R7") (pin "1") (pinfunction "1_1") (pintype "bidirectional"))
    )
    (net (code "23") (name "Net-(IC1-OUT)") (class "Default")
      (node (ref "C7") (pin "1") (pinfunction "1_1") (pintype "bidirectional"))
      (node (ref "IC1") (pin "4") (pinfunction "OUT_4") (pintype "output"))
      (node (ref "R7") (pin "2") (pinfunction "2_2") (pintype "bidirectional"))
    )
    (net (code "24") (name "Net-(J1-Pad3)") (class "Default")
      (node (ref "J1") (pin "3") (pinfunction "3_3") (pintype "bidirectional"))
      (node (ref "J2") (pin "2") (pinfunction "2_2") (pintype "bidirectional"))
    )
    (net (code "25") (name "Net-(J2-Pad3)") (class "Default")
      (node (ref "J2") (pin "3") (pinfunction "3_3") (pintype "bidirectional"))
      (node (ref "J3") (pin "2") (pinfunction "2_2") (pintype "bidirectional"))
    )
    (net (code "26") (name "Net-(J3-Pad3)") (class "Default")
      (node (ref "J3") (pin "3") (pinfunction "3_3") (pintype "bidirectional"))
      (node (ref "J4") (pin "2") (pinfunction "2_2") (pintype "bidirectional"))
    )
    (net (code "27") (name "Net-(J4-Pad3)") (class "Default")
      (node (ref "J4") (pin "3") (pinfunction "3_3") (pintype "bidirectional"))
      (node (ref "J5") (pin "2") (pinfunction "2_2") (pintype "bidirectional"))
    )
    (net (code "28") (name "Net-(J5-Pad3)") (class "Default")
      (node (ref "J5") (pin "3") (pinfunction "3_3") (pintype "bidirectional"))
      (node (ref "J6") (pin "2") (pinfunction "2_2") (pintype "bidirectional"))
    )
    (net (code "29") (name "Net-(J6-Pad3)") (class "Default")
      (node (ref "J6") (pin "3") (pinfunction "3_3") (pintype "bidirectional"))
      (node (ref "J7") (pin "2") (pinfunction "2_2") (pintype "bidirectional"))
    )
    (net (code "30") (name "Net-(J7-Pad3)") (class "Default")
      (node (ref "J7") (pin "3") (pinfunction "3_3") (pintype "bidirectional"))
      (node (ref "J8") (pin "2") (pinfunction "2_2") (pintype "bidirectional"))
    )
    (net (code "31") (name "Net-(J8-Pad3)") (class "Default")
      (node (ref "J8") (pin "3") (pinfunction "3_3") (pintype "bidirectional"))
      (node (ref "J9") (pin "2") (pinfunction "2_2") (pintype "bidirectional"))
    )
    (net (code "32") (name "Net-(J10-Pad2)") (class "Default")
      (node (ref "J10") (pin "2") (pinfunction "2_2") (pintype "bidirectional"))
      (node (ref "J9") (pin "3") (pinfunction "3_3") (pintype "bidirectional"))
    )
    (net (code "33") (name "Net-(J10-Pad3)") (class "Default")
      (node (ref "J10") (pin "3") (pinfunction "3_3") (pintype "bidirectional"))
      (node (ref "J11") (pin "2") (pinfunction "2_2") (pintype "bidirectional"))
    )
    (net (code "34") (name "Net-(J11-Pad3)") (class "Default")
      (node (ref "J11") (pin "3") (pinfunction "3_3") (pintype "bidirectional"))
      (node (ref "J12") (pin "2") (pinfunction "2_2") (pintype "bidirectional"))
    )
    (net (code "35") (name "Net-(J12-Pad3)") (class "Default")
      (node (ref "J12") (pin "3") (pinfunction "3_3") (pintype "bidirectional"))
      (node (ref "J13") (pin "2") (pinfunction "2_2") (pintype "bidirectional"))
    )
    (net (code "36") (name "Net-(J13-Pad3)") (class "Default")
      (node (ref "J13") (pin "3") (pinfunction "3_3") (pintype "bidirectional"))
      (node (ref "J14") (pin "2") (pinfunction "2_2") (pintype "bidirectional"))
    )
    (net (code "37") (name "Net-(J14-Pad3)") (class "Default")
      (node (ref "J14") (pin "3") (pinfunction "3_3") (pintype "bidirectional"))
      (node (ref "J15") (pin "2") (pinfunction "2_2") (pintype "bidirectional"))
    )
    (net (code "38") (name "Net-(J15-Pad3)") (class "Default")
      (node (ref "J15") (pin "3") (pinfunction "3_3") (pintype "bidirectional"))
      (node (ref "J16") (pin "2") (pinfunction "2_2") (pintype "bidirectional"))
    )
    (net (code "39") (name "Net-(J16-Pad3)") (class "Default")
      (node (ref "J16") (pin "3") (pinfunction "3_3") (pintype "bidirectional"))
      (node (ref "J17") (pin "2") (pinfunction "2_2") (pintype "bidirectional"))
    )
    (net (code "40") (name "Net-(J17-Pad3)") (class "Default")
      (node (ref "J17") (pin "3") (pinfunction "3_3") (pintype "bidirectional"))
      (node (ref "J18") (pin "2") (pinfunction "2_2") (pintype "bidirectional"))
    )
    (net (code "41") (name "Net-(J18-Pad3)") (class "Default")
      (node (ref "J18") (pin "3") (pinfunction "3_3") (pintype "bidirectional"))
      (node (ref "J19") (pin "2") (pinfunction "2_2") (pintype "bidirectional"))
    )
    (net (code "42") (name "Net-(J19-Pad3)") (class "Default")
      (node (ref "J19") (pin "3") (pinfunction "3_3") (pintype "bidirectional"))
      (node (ref "J20") (pin "2") (pinfunction "2_2") (pintype "bidirectional"))
    )
    (net (code "43") (name "Net-(J20-Pad3)") (class "Default")
      (node (ref "J20") (pin "3") (pinfunction "3_3") (pintype "bidirectional"))
      (node (ref "J21") (pin "2") (pinfunction "2_2") (pintype "bidirectional"))
    )
    (net (code "44") (name "Net-(J21-Pad3)") (class "Default")
      (node (ref "J21") (pin "3") (pinfunction "3_3") (pintype "bidirectional"))
      (node (ref "J22") (pin "2") (pinfunction "2_2") (pintype "bidirectional"))
    )
    (net (code "45") (name "Net-(J22-Pad3)") (class "Default")
      (node (ref "J22") (pin "3") (pinfunction "3_3") (pintype "bidirectional"))
      (node (ref "J23") (pin "2") (pinfunction "2_2") (pintype "bidirectional"))
    )
    (net (code "46") (name "Net-(J23-Pad3)") (class "Default")
      (node (ref "J23") (pin "3") (pinfunction "3_3") (pintype "bidirectional"))
      (node (ref "J24") (pin "2") (pinfunction "2_2") (pintype "bidirectional"))
    )
    (net (code "47") (name "Net-(J24-Pad3)") (class "Default")
      (node (ref "J24") (pin "3") (pinfunction "3_3") (pintype "bidirectional"))
      (node (ref "J25") (pin "2") (pinfunction "2_2") (pintype "bidirectional"))
    )
    (net (code "48") (name "Net-(J25-Pad3)") (class "Default")
      (node (ref "J25") (pin "3") (pinfunction "3_3") (pintype "bidirectional"))
      (node (ref "J26") (pin "2") (pinfunction "2_2") (pintype "bidirectional"))
    )
    (net (code "49") (name "Net-(J26-Pad3)") (class "Default")
      (node (ref "J26") (pin "3") (pinfunction "3_3") (pintype "bidirectional"))
      (node (ref "J27") (pin "2") (pinfunction "2_2") (pintype "bidirectional"))
    )
    (net (code "50") (name "Net-(J27-Pad3)") (class "Default")
      (node (ref "J27") (pin "3") (pinfunction "3_3") (pintype "bidirectional"))
      (node (ref "J28") (pin "2") (pinfunction "2_2") (pintype "bidirectional"))
    )
    (net (code "51") (name "Net-(J28-Pad3)") (class "Default")
      (node (ref "J28") (pin "3") (pinfunction "3_3") (pintype "bidirectional"))
      (node (ref "J29") (pin "2") (pinfunction "2_2") (pintype "bidirectional"))
    )
    (net (code "52") (name "Net-(J29-Pad3)") (class "Default")
      (node (ref "J29") (pin "3") (pinfunction "3_3") (pintype "bidirectional"))
      (node (ref "J30") (pin "2") (pinfunction "2_2") (pintype "bidirectional"))
    )
    (net (code "53") (name "Net-(J30-Pad3)") (class "Default")
      (node (ref "J30") (pin "3") (pinfunction "3_3") (pintype "bidirectional"))
      (node (ref "J31") (pin "2") (pinfunction "2_2") (pintype "bidirectional"))
    )
    (net (code "54") (name "Net-(J31-Pad3)") (class "Default")
      (node (ref "J31") (pin "3") (pinfunction "3_3") (pintype "bidirectional"))
      (node (ref "J32") (pin "2") (pinfunction "2_2") (pintype "bidirectional"))
    )
    (net (code "55") (name "Net-(J32-Pad3)") (class "Default")
      (node (ref "J32") (pin "3") (pinfunction "3_3") (pintype "bidirectional"))
      (node (ref "J33") (pin "2") (pinfunction "2_2") (pintype "bidirectional"))
    )
    (net (code "56") (name "Net-(J33-Pad3)") (class "Default")
      (node (ref "J33") (pin "3") (pinfunction "3_3") (pintype "bidirectional"))
      (node (ref "J34") (pin "2") (pinfunction "2_2") (pintype "bidirectional"))
    )
    (net (code "57") (name "Net-(J34-Pad3)") (class "Default")
      (node (ref "J34") (pin "3") (pinfunction "3_3") (pintype "bidirectional"))
      (node (ref "J35") (pin "2") (pinfunction "2_2") (pintype "bidirectional"))
    )
    (net (code "58") (name "Net-(J35-Pad3)") (class "Default")
      (node (ref "J35") (pin "3") (pinfunction "3_3") (pintype "bidirectional"))
      (node (ref "J36") (pin "2") (pinfunction "2_2") (pintype "bidirectional"))
    )
    (net (code "59") (name "Net-(J36-Pad3)") (class "Default")
      (node (ref "J36") (pin "3") (pinfunction "3_3") (pintype "bidirectional"))
      (node (ref "J37") (pin "2") (pinfunction "2_2") (pintype "bidirectional"))
    )
    (net (code "60") (name "Net-(J37-Pad3)") (class "Default")
      (node (ref "J37") (pin "3") (pinfunction "3_3") (pintype "bidirectional"))
      (node (ref "J38") (pin "2") (pinfunction "2_2") (pintype "bidirectional"))
    )
    (net (code "61") (name "Net-(J38-Pad3)") (class "Default")
      (node (ref "J38") (pin "3") (pinfunction "3_3") (pintype "bidirectional"))
      (node (ref "J39") (pin "2") (pinfunction "2_2") (pintype "bidirectional"))
    )
    (net (code "62") (name "Net-(J39-Pad3)") (class "Default")
      (node (ref "J39") (pin "3") (pinfunction "3_3") (pintype "bidirectional"))
      (node (ref "J40") (pin "2") (pinfunction "2_2") (pintype "bidirectional"))
    )
    (net (code "63") (name "Net-(J40-Pad3)") (class "Default")
      (node (ref "J40") (pin "3") (pinfunction "3_3") (pintype "bidirectional"))
      (node (ref "J41") (pin "2") (pinfunction "2_2") (pintype "bidirectional"))
    )
    (net (code "64") (name "Net-(J41-Pad3)") (class "Default")
      (node (ref "J41") (pin "3") (pinfunction "3_3") (pintype "bidirectional"))
      (node (ref "J42") (pin "2") (pinfunction "2_2") (pintype "bidirectional"))
    )
    (net (code "65") (name "Net-(J42-Pad3)") (class "Default")
      (node (ref "J42") (pin "3") (pinfunction "3_3") (pintype "bidirectional"))
      (node (ref "J43") (pin "2") (pinfunction "2_2") (pintype "bidirectional"))
    )
    (net (code "66") (name "Net-(J43-Pad3)") (class "Default")
      (node (ref "J43") (pin "3") (pinfunction "3_3") (pintype "bidirectional"))
      (node (ref "J44") (pin "2") (pinfunction "2_2") (pintype "bidirectional"))
    )
    (net (code "67") (name "Net-(J44-Pad3)") (class "Default")
      (node (ref "J44") (pin "3") (pinfunction "3_3") (pintype "bidirectional"))
      (node (ref "J45") (pin "2") (pinfunction "2_2") (pintype "bidirectional"))
    )
    (net (code "68") (name "Net-(J45-Pad3)") (class "Default")
      (node (ref "J45") (pin "3") (pinfunction "3_3") (pintype "bidirectional"))
      (node (ref "J46") (pin "2") (pinfunction "2_2") (pintype "bidirectional"))
    )
    (net (code "69") (name "Net-(J46-Pad3)") (class "Default")
      (node (ref "J46") (pin "3") (pinfunction "3_3") (pintype "bidirectional"))
      (node (ref "J47") (pin "2") (pinfunction "2_2") (pintype "bidirectional"))
    )
    (net (code "70") (name "Net-(J47-Pad3)") (class "Default")
      (node (ref "J47") (pin "3") (pinfunction "3_3") (pintype "bidirectional"))
      (node (ref "J48") (pin "2") (pinfunction "2_2") (pintype "bidirectional"))
    )
    (net (code "71") (name "Net-(J48-Pad3)") (class "Default")
      (node (ref "J48") (pin "3") (pinfunction "3_3") (pintype "bidirectional"))
      (node (ref "J49") (pin "2") (pinfunction "2_2") (pintype "bidirectional"))
    )
    (net (code "72") (name "Net-(J49-Pad3)") (class "Default")
      (node (ref "J49") (pin "3") (pinfunction "3_3") (pintype "bidirectional"))
      (node (ref "J50") (pin "2") (pinfunction "2_2") (pintype "bidirectional"))
    )
    (net (code "73") (name "Net-(J50-Pad3)") (class "Default")
      (node (ref "J50") (pin "3") (pinfunction "3_3") (pintype "bidirectional"))
      (node (ref "J51") (pin "2") (pinfunction "2_2") (pintype "bidirectional"))
    )
    (net (code "74") (name "Net-(J51-Pad3)") (class "Default")
      (node (ref "J51") (pin "3") (pinfunction "3_3") (pintype "bidirectional"))
      (node (ref "J52") (pin "2") (pinfunction "2_2") (pintype "bidirectional"))
    )
    (net (code "75") (name "Net-(J52-Pad3)") (class "Default")
      (node (ref "J52") (pin "3") (pinfunction "3_3") (pintype "bidirectional"))
      (node (ref "J53") (pin "2") (pinfunction "2_2") (pintype "bidirectional"))
    )
    (net (code "76") (name "Net-(J53-Pad3)") (class "Default")
      (node (ref "J53") (pin "3") (pinfunction "3_3") (pintype "bidirectional"))
      (node (ref "J54") (pin "2") (pinfunction "2_2") (pintype "bidirectional"))
    )
    (net (code "77") (name "Net-(J54-Pad3)") (class "Default")
      (node (ref "J54") (pin "3") (pinfunction "3_3") (pintype "bidirectional"))
      (node (ref "J55") (pin "2") (pinfunction "2_2") (pintype "bidirectional"))
    )
    (net (code "78") (name "Net-(J55-Pad3)") (class "Default")
      (node (ref "J55") (pin "3") (pinfunction "3_3") (pintype "bidirectional"))
      (node (ref "J56") (pin "2") (pinfunction "2_2") (pintype "bidirectional"))
    )
    (net (code "79") (name "Net-(J56-Pad3)") (class "Default")
      (node (ref "J56") (pin "3") (pinfunction "3_3") (pintype "bidirectional"))
      (node (ref "J57") (pin "2") (pinfunction "2_2") (pintype "bidirectional"))
    )
    (net (code "80") (name "Net-(J57-Pad3)") (class "Default")
      (node (ref "J57") (pin "3") (pinfunction "3_3") (pintype "bidirectional"))
      (node (ref "J58") (pin "2") (pinfunction "2_2") (pintype "bidirectional"))
    )
    (net (code "81") (name "Net-(J58-Pad3)") (class "Default")
      (node (ref "J58") (pin "3") (pinfunction "3_3") (pintype "bidirectional"))
      (node (ref "J59") (pin "2") (pinfunction "2_2") (pintype "bidirectional"))
    )
    (net (code "82") (name "Net-(J59-Pad3)") (class "Default")
      (node (ref "J59") (pin "3") (pinfunction "3_3") (pintype "bidirectional"))
      (node (ref "J60") (pin "2") (pinfunction "2_2") (pintype "bidirectional"))
    )
    (net (code "83") (name "Net-(J60-Pad3)") (class "Default")
      (node (ref "J60") (pin "3") (pinfunction "3_3") (pintype "bidirectional"))
      (node (ref "J61") (pin "2") (pinfunction "2_2") (pintype "bidirectional"))
    )
    (net (code "84") (name "Net-(J61-Pad3)") (class "Default")
      (node (ref "J61") (pin "3") (pinfunction "3_3") (pintype "bidirectional"))
      (node (ref "J62") (pin "2") (pinfunction "2_2") (pintype "bidirectional"))
    )
    (net (code "85") (name "Net-(J62-Pad3)") (class "Default")
      (node (ref "J62") (pin "3") (pinfunction "3_3") (pintype "bidirectional"))
      (node (ref "J63") (pin "2") (pinfunction "2_2") (pintype "bidirectional"))
    )
    (net (code "86") (name "Net-(J63-Pad3)") (class "Default")
      (node (ref "J63") (pin "3") (pinfunction "3_3") (pintype "bidirectional"))
      (node (ref "J64") (pin "2") (pinfunction "2_2") (pintype "bidirectional"))
    )
    (net (code "87") (name "Net-(Q3-D)") (class "Default")
      (node (ref "C6") (pin "2") (pinfunction "2_2") (pintype "bidirectional"))
      (node (ref "Q3") (pin "3") (pinfunction "D_3") (pintype "passive"))
      (node (ref "R8") (pin "1") (pinfunction "1_1") (pintype "bidirectional"))
    )
    (net (code "88") (name "Net-(Q3-G)") (class "Default")
      (node (ref "C5") (pin "1") (pinfunction "1_1") (pintype "bidirectional"))
      (node (ref "Q3") (pin "1") (pinfunction "G_1") (pintype "passive"))
      (node (ref "R9") (pin "2") (pinfunction "2_2") (pintype "bidirectional"))
    )
    (net (code "89") (name "SOUND") (class "Default")
      (node (ref "A1") (pin "A0") (pinfunction "A0_A0") (pintype "bidirectional"))
      (node (ref "C7") (pin "2") (pinfunction "2_2") (pintype "bidirectional"))
      (node (ref "JP1") (pin "10") (pinfunction "10_10") (pintype "passive"))
      (node (ref "R11") (pin "1") (pinfunction "1_1") (pintype "bidirectional"))
      (node (ref "R12") (pin "2") (pinfunction "2_2") (pintype "bidirectional"))
    )
    (net (code "90") (name "SWITCH") (class "Default")
      (node (ref "A1") (pin "D4") (pinfunction "D4_D4") (pintype "bidirectional"))
      (node (ref "JP2") (pin "10") (pinfunction "10_10") (pintype "passive"))
      (node (ref "R6") (pin "2") (pinfunction "2_2") (pintype "bidirectional"))
      (node (ref "S1") (pin "2") (pinfunction "P_2") (pintype "passive"))
    )
    (net (code "91") (name "V+") (class "Default")
      (node (ref "A1") (pin "A4") (pinfunction "A4_A4") (pintype "bidirectional"))
      (node (ref "C1") (pin "+") (pinfunction "1_+") (pintype "bidirectional"))
      (node (ref "C2") (pin "+") (pinfunction "1_+") (pintype "bidirectional"))
      (node (ref "C3") (pin "2") (pinfunction "2_2") (pintype "bidirectional"))
      (node (ref "FDD6637") (pin "3") (pinfunction "D_3") (pintype "passive"))
      (node (ref "J1") (pin "1") (pinfunction "1_1") (pintype "bidirectional"))
      (node (ref "J10") (pin "1") (pinfunction "1_1") (pintype "bidirectional"))
      (node (ref "J11") (pin "1") (pinfunction "1_1") (pintype "bidirectional"))
      (node (ref "J12") (pin "1") (pinfunction "1_1") (pintype "bidirectional"))
      (node (ref "J13") (pin "1") (pinfunction "1_1") (pintype "bidirectional"))
      (node (ref "J14") (pin "1") (pinfunction "1_1") (pintype "bidirectional"))
      (node (ref "J15") (pin "1") (pinfunction "1_1") (pintype "bidirectional"))
      (node (ref "J16") (pin "1") (pinfunction "1_1") (pintype "bidirectional"))
      (node (ref "J17") (pin "1") (pinfunction "1_1") (pintype "bidirectional"))
      (node (ref "J18") (pin "1") (pinfunction "1_1") (pintype "bidirectional"))
      (node (ref "J19") (pin "1") (pinfunction "1_1") (pintype "bidirectional"))
      (node (ref "J2") (pin "1") (pinfunction "1_1") (pintype "bidirectional"))
      (node (ref "J20") (pin "1") (pinfunction "1_1") (pintype "bidirectional"))
      (node (ref "J21") (pin "1") (pinfunction "1_1") (pintype "bidirectional"))
      (node (ref "J22") (pin "1") (pinfunction "1_1") (pintype "bidirectional"))
      (node (ref "J23") (pin "1") (pinfunction "1_1") (pintype "bidirectional"))
      (node (ref "J24") (pin "1") (pinfunction "1_1") (pintype "bidirectional"))
      (node (ref "J25") (pin "1") (pinfunction "1_1") (pintype "bidirectional"))
      (node (ref "J26") (pin "1") (pinfunction "1_1") (pintype "bidirectional"))
      (node (ref "J27") (pin "1") (pinfunction "1_1") (pintype "bidirectional"))
      (node (ref "J28") (pin "1") (pinfunction "1_1") (pintype "bidirectional"))
      (node (ref "J29") (pin "1") (pinfunction "1_1") (pintype "bidirectional"))
      (node (ref "J3") (pin "1") (pinfunction "1_1") (pintype "bidirectional"))
      (node (ref "J30") (pin "1") (pinfunction "1_1") (pintype "bidirectional"))
      (node (ref "J31") (pin "1") (pinfunction "1_1") (pintype "bidirectional"))
      (node (ref "J32") (pin "1") (pinfunction "1_1") (pintype "bidirectional"))
      (node (ref "J33") (pin "1") (pinfunction "1_1") (pintype "bidirectional"))
      (node (ref "J34") (pin "1") (pinfunction "1_1") (pintype "bidirectional"))
      (node (ref "J35") (pin "1") (pinfunction "1_1") (pintype "bidirectional"))
      (node (ref "J36") (pin "1") (pinfunction "1_1") (pintype "bidirectional"))
      (node (ref "J37") (pin "1") (pinfunction "1_1") (pintype "bidirectional"))
      (node (ref "J38") (pin "1") (pinfunction "1_1") (pintype "bidirectional"))
      (node (ref "J39") (pin "1") (pinfunction "1_1") (pintype "bidirectional"))
      (node (ref "J4") (pin "1") (pinfunction "1_1") (pintype "bidirectional"))
      (node (ref "J40") (pin "1") (pinfunction "1_1") (pintype "bidirectional"))
      (node (ref "J41") (pin "1") (pinfunction "1_1") (pintype "bidirectional"))
      (node (ref "J42") (pin "1") (pinfunction "1_1") (pintype "bidirectional"))
      (node (ref "J43") (pin "1") (pinfunction "1_1") (pintype "bidirectional"))
      (node (ref "J44") (pin "1") (pinfunction "1_1") (pintype "bidirectional"))
      (node (ref "J45") (pin "1") (pinfunction "1_1") (pintype "bidirectional"))
      (node (ref "J46") (pin "1") (pinfunction "1_1") (pintype "bidirectional"))
      (node (ref "J47") (pin "1") (pinfunction "1_1") (pintype "bidirectional"))
      (node (ref "J48") (pin "1") (pinfunction "1_1") (pintype "bidirectional"))
      (node (ref "J49") (pin "1") (pinfunction "1_1") (pintype "bidirectional"))
      (node (ref "J5") (pin "1") (pinfunction "1_1") (pintype "bidirectional"))
      (node (ref "J50") (pin "1") (pinfunction "1_1") (pintype "bidirectional"))
      (node (ref "J51") (pin "1") (pinfunction "1_1") (pintype "bidirectional"))
      (node (ref "J52") (pin "1") (pinfunction "1_1") (pintype "bidirectional"))
      (node (ref "J53") (pin "1") (pinfunction "1_1") (pintype "bidirectional"))
      (node (ref "J54") (pin "1") (pinfunction "1_1") (pintype "bidirectional"))
      (node (ref "J55") (pin "1") (pinfunction "1_1") (pintype "bidirectional"))
      (node (ref "J56") (pin "1") (pinfunction "1_1") (pintype "bidirectional"))
      (node (ref "J57") (pin "1") (pinfunction "1_1") (pintype "bidirectional"))
      (node (ref "J58") (pin "1") (pinfunction "1_1") (pintype "bidirectional"))
      (node (ref "J59") (pin "1") (pinfunction "1_1") (pintype "bidirectional"))
      (node (ref "J6") (pin "1") (pinfunction "1_1") (pintype "bidirectional"))
      (node (ref "J60") (pin "1") (pinfunction "1_1") (pintype "bidirectional"))
      (node (ref "J61") (pin "1") (pinfunction "1_1") (pintype "bidirectional"))
      (node (ref "J62") (pin "1") (pinfunction "1_1") (pintype "bidirectional"))
      (node (ref "J63") (pin "1") (pinfunction "1_1") (pintype "bidirectional"))
      (node (ref "J64") (pin "1") (pinfunction "1_1") (pintype "bidirectional"))
      (node (ref "J7") (pin "1") (pinfunction "1_1") (pintype "bidirectional"))
      (node (ref "J8") (pin "1") (pinfunction "1_1") (pintype "bidirectional"))
      (node (ref "J9") (pin "1") (pinfunction "1_1") (pintype "bidirectional"))
      (node (ref "JP1") (pin "6") (pinfunction "6_6") (pintype "passive"))
    )
    (net (code "92") (name "XOUT") (class "Default")
      (node (ref "A1") (pin "A1") (pinfunction "A1_A1") (pintype "bidirectional"))
      (node (ref "C11") (pin "2") (pinfunction "2_2") (pintype "bidirectional"))
      (node (ref "JP1") (pin "9") (pinfunction "9_9") (pintype "passive"))
      (node (ref "U2") (pin "X") (pinfunction "X_X") (pintype "bidirectional"))
    )
    (net (code "93") (name "YOUT") (class "Default")
      (node (ref "A1") (pin "A2") (pinfunction "A2_A2") (pintype "bidirectional"))
      (node (ref "C10") (pin "2") (pinfunction "2_2") (pintype "bidirectional"))
      (node (ref "JP1") (pin "8") (pinfunction "8_8") (pintype "passive"))
      (node (ref "U2") (pin "Y") (pinfunction "Y_Y") (pintype "bidirectional"))
    )
    (net (code "94") (name "ZOUT") (class "Default")
      (node (ref "A1") (pin "A3") (pinfunction "A3_A3") (pintype "bidirectional"))
      (node (ref "C9") (pin "2") (pinfunction "2_2") (pintype "bidirectional"))
      (node (ref "JP1") (pin "7") (pinfunction "7_7") (pintype "passive"))
      (node (ref "U2") (pin "Z") (pinfunction "Z_Z") (pintype "bidirectional"))
    )
    (net (code "95") (name "unconnected-(A1-1-Pad100)") (class "Default")
      (node (ref "A1") (pin "100") (pinfunction "1_100") (pintype "bidirectional"))
    )
    (net (code "96") (name "unconnected-(A1-PadA5)") (class "Default")
      (node (ref "A1") (pin "A5") (pinfunction "A5_A5") (pintype "bidirectional"))
    )
    (net (code "97") (name "unconnected-(A1-PadD0)") (class "Default")
      (node (ref "A1") (pin "D0") (pinfunction "D0_D0") (pintype "bidirectional"))
    )
    (net (code "98") (name "unconnected-(A1-PadD1)") (class "Default")
      (node (ref "A1") (pin "D1") (pinfunction "D1_D1") (pintype "bidirectional"))
    )
    (net (code "99") (name "unconnected-(A1-PadD5)") (class "Default")
      (node (ref "A1") (pin "D5") (pinfunction "D5_D5") (pintype "bidirectional"))
    )
    (net (code "100") (name "unconnected-(A1-PadD6)") (class "Default")
      (node (ref "A1") (pin "D6") (pinfunction "D6_D6") (pintype "bidirectional"))
    )
    (net (code "101") (name "unconnected-(A1-PadD7)") (class "Default")
      (node (ref "A1") (pin "D7") (pinfunction "D7_D7") (pintype "bidirectional"))
    )
    (net (code "102") (name "unconnected-(A1-PadD8)") (class "Default")
      (node (ref "A1") (pin "D8") (pinfunction "D8_D8") (pintype "bidirectional"))
    )
    (net (code "103") (name "unconnected-(A1-PadD9)") (class "Default")
      (node (ref "A1") (pin "D9") (pinfunction "D9_D9") (pintype "bidirectional"))
    )
    (net (code "104") (name "unconnected-(A1-PadD10)") (class "Default")
      (node (ref "A1") (pin "D10") (pinfunction "D10_D10") (pintype "bidirectional"))
    )
    (net (code "105") (name "unconnected-(A1-PadD11)") (class "Default")
      (node (ref "A1") (pin "D11") (pinfunction "D11_D11") (pintype "bidirectional"))
    )
    (net (code "106") (name "unconnected-(A1-PadD12)") (class "Default")
      (node (ref "A1") (pin "D12") (pinfunction "D12_D12") (pintype "bidirectional"))
    )
    (net (code "107") (name "unconnected-(A1-PadD13)") (class "Default")
      (node (ref "A1") (pin "D13") (pinfunction "D13_D13") (pintype "bidirectional"))
    )
    (net (code "108") (name "unconnected-(A1-PadIOREF)") (class "Default")
      (node (ref "A1") (pin "IOREF") (pinfunction "IOREF_IOREF") (pintype "bidirectional"))
    )
    (net (code "109") (name "unconnected-(A1-PadRESET)") (class "Default")
      (node (ref "A1") (pin "RESET") (pinfunction "RESET_RESET") (pintype "bidirectional"))
    )
    (net (code "110") (name "unconnected-(A1-PadVIN)") (class "Default")
      (node (ref "A1") (pin "VIN") (pinfunction "VIN_VIN") (pintype "bidirectional"))
    )
    (net (code "111") (name "unconnected-(J64-Pad3)") (class "Default")
      (node (ref "J64") (pin "3") (pinfunction "3_3") (pintype "bidirectional"))
    )
    (net (code "112") (name "unconnected-(S1-O-Pad1)") (class "Default")
      (node (ref "S1") (pin "1") (pinfunction "O_1") (pintype "passive"))
    )
    (net (code "113") (name "unconnected-(SV1C-S-Pad3)") (class "Default")
      (node (ref "SV1") (pin "3") (pinfunction "S_3") (pintype "passive"))
    )
    (net (code "114") (name "unconnected-(U2-PadNC1)") (class "Default")
      (node (ref "U2") (pin "NC1") (pinfunction "NC1_NC1") (pintype "bidirectional"))
    )
    (net (code "115") (name "unconnected-(U2-PadNC2)") (class "Default")
      (node (ref "U2") (pin "NC2") (pinfunction "NC2_NC2") (pintype "bidirectional"))
    )
    (net (code "116") (name "unconnected-(U2-PadNC3)") (class "Default")
      (node (ref "U2") (pin "NC3") (pinfunction "NC3_NC3") (pintype "bidirectional"))
    )
    (net (code "117") (name "unconnected-(U2-PadNC4)") (class "Default")
      (node (ref "U2") (pin "NC4") (pinfunction "NC4_NC4") (pintype "bidirectional"))
    )
    (net (code "118") (name "unconnected-(U2-PadNC5)") (class "Default")
      (node (ref "U2") (pin "NC5") (pinfunction "NC5_NC5") (pintype "bidirectional"))
    )
    (net (code "119") (name "unconnected-(U2-PadNC6)") (class "Default")
      (node (ref "U2") (pin "NC6") (pinfunction "NC6_NC6") (pintype "bidirectional"))
    )
    (net (code "120") (name "unconnected-(U2-PadST)") (class "Default")
      (node (ref "U2") (pin "ST") (pinfunction "ST_ST") (pintype "bidirectional"))
    )
  )
)
